# M4_Sensors.net
KiCad netlist of a schematic drawn in Altium Designer
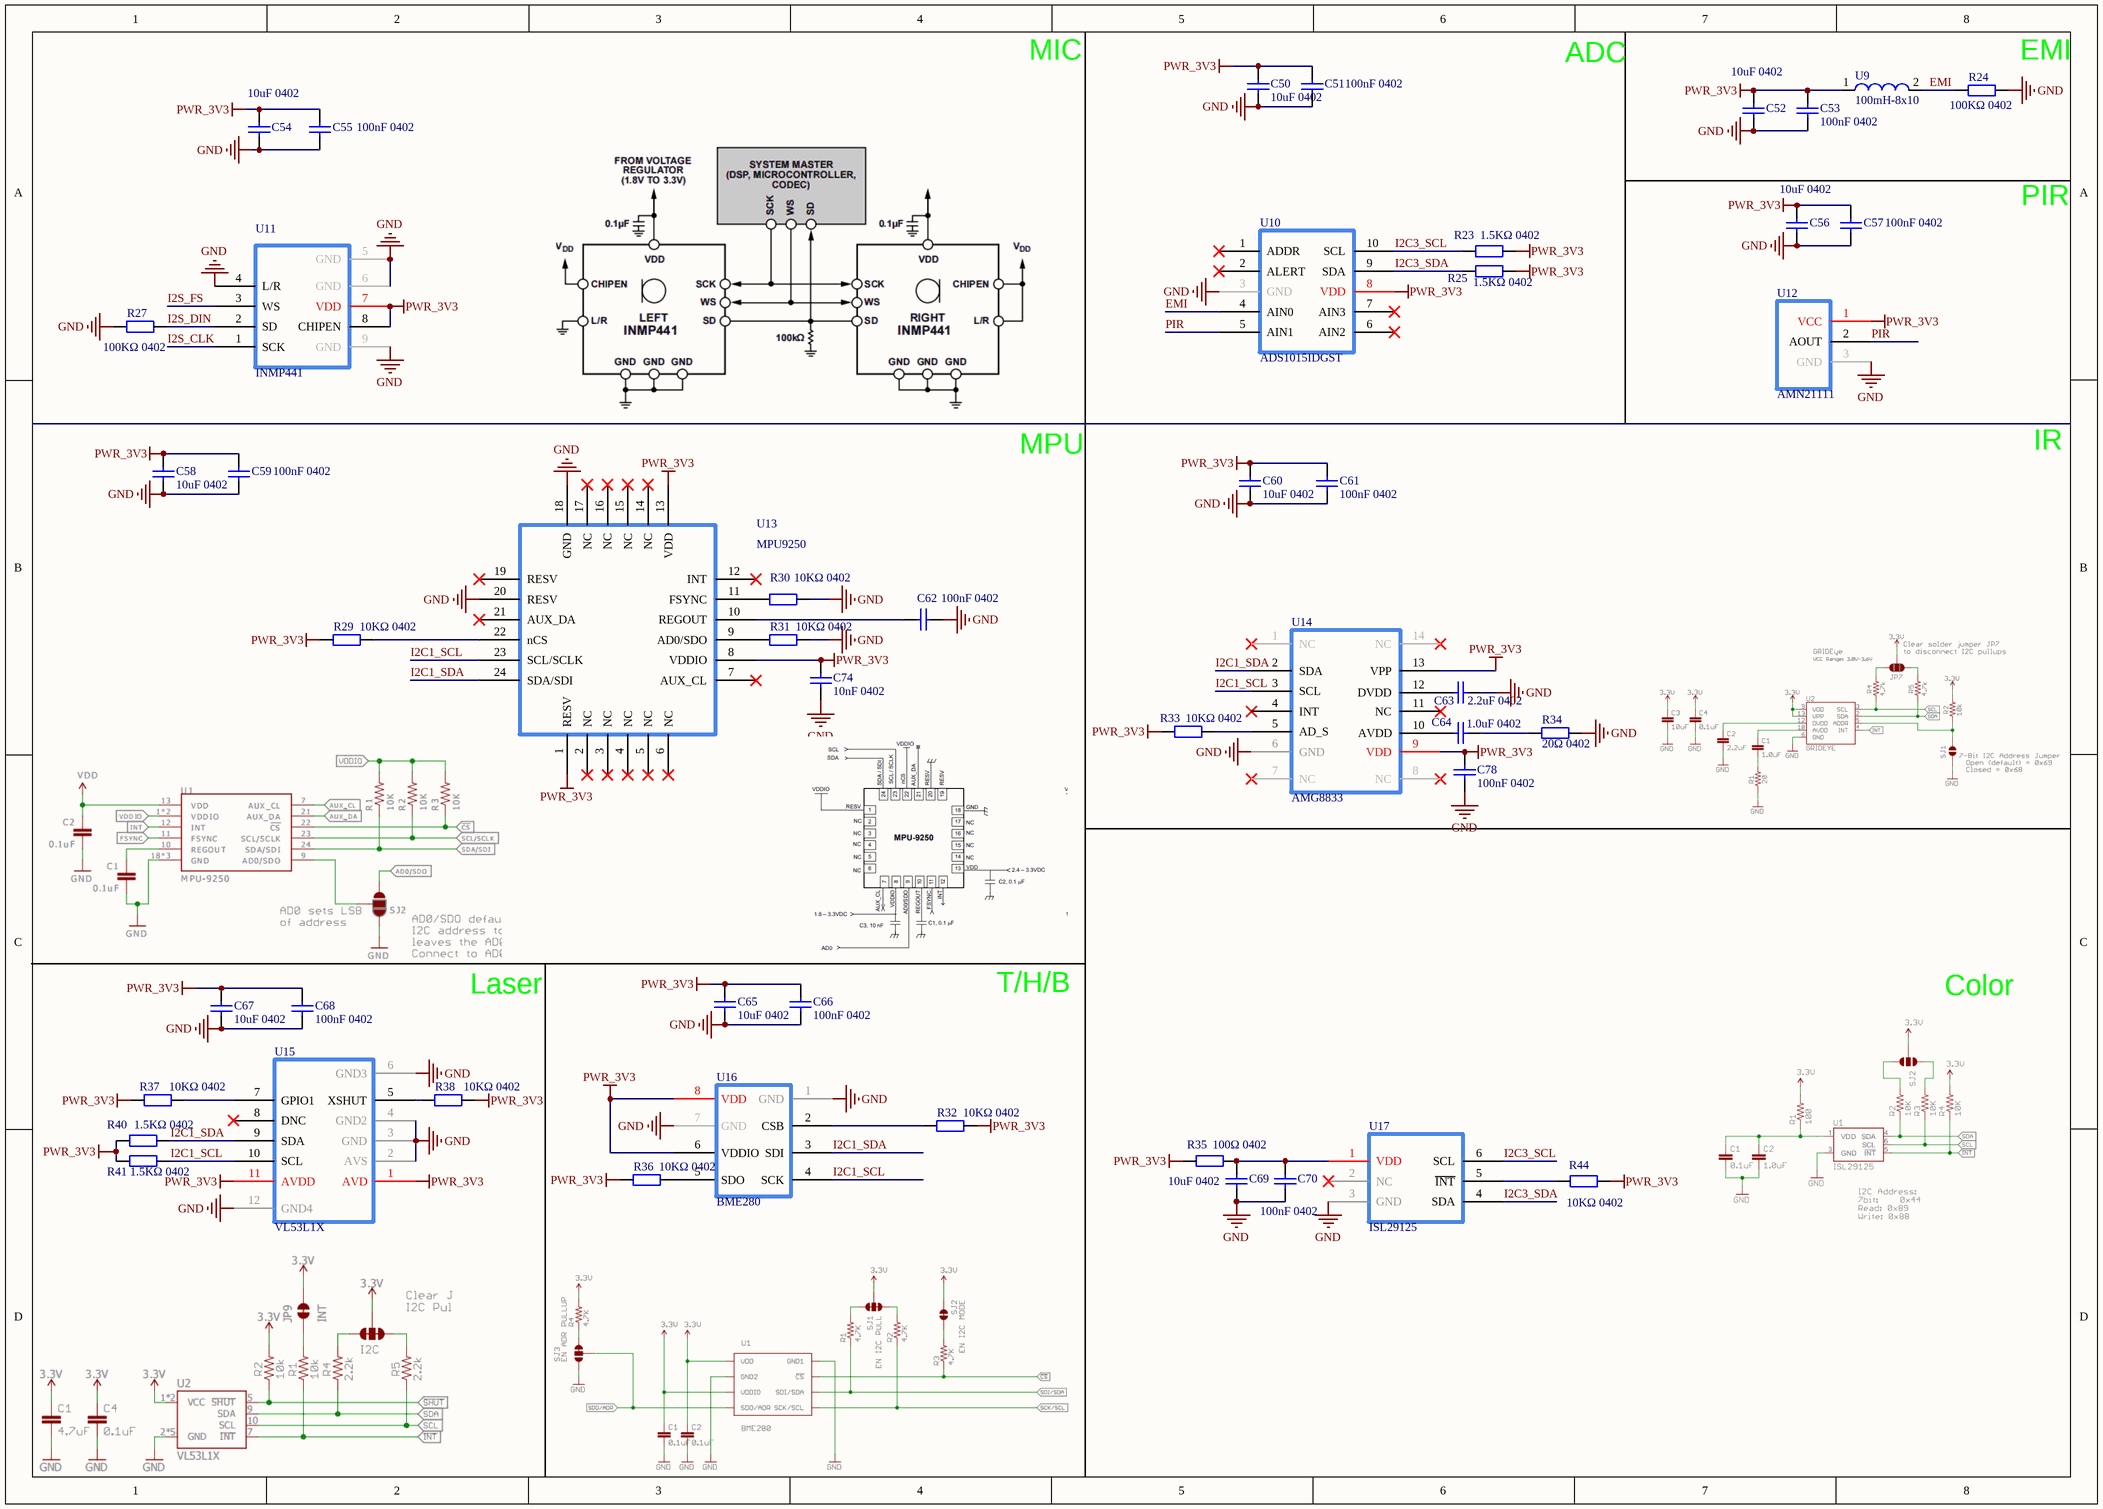
[diagram p0: M4_Sensors.SchDoc]

(export (version "E")
  (design (tool "Eeschema 10.0.6"))
  (components
    (comp (ref "C50")
      (value "10uF 0402")
      (footprint "0402_C")
      (description "贴片电容")
      (libsource (lib "Miscellaneous Devices LC") (part "0402 10uF (106) 20% 6.3V"))
    )
    (comp (ref "C51")
      (value "100nF 0402")
      (footprint "0402_C")
      (description "贴片电容")
      (libsource (lib "Miscellaneous Devices LC") (part "0402 100nF (104) 10% 16V"))
    )
    (comp (ref "C52")
      (value "10uF 0402")
      (footprint "0402_C")
      (description "贴片电容")
      (libsource (lib "Miscellaneous Devices LC") (part "0402 10uF (106) 20% 6.3V"))
    )
    (comp (ref "C53")
      (value "100nF 0402")
      (footprint "0402_C")
      (description "贴片电容")
      (libsource (lib "Miscellaneous Devices LC") (part "0402 100nF (104) 10% 16V"))
    )
    (comp (ref "C54")
      (value "10uF 0402")
      (footprint "0402_C")
      (description "贴片电容")
      (libsource (lib "Miscellaneous Devices LC") (part "0402 10uF (106) 20% 6.3V"))
    )
    (comp (ref "C55")
      (value "100nF 0402")
      (footprint "0402_C")
      (description "贴片电容")
      (libsource (lib "Miscellaneous Devices LC") (part "0402 100nF (104) 10% 16V"))
    )
    (comp (ref "C56")
      (value "10uF 0402")
      (footprint "0402_C")
      (description "贴片电容")
      (libsource (lib "Miscellaneous Devices LC") (part "0402 10uF (106) 20% 6.3V"))
    )
    (comp (ref "C57")
      (value "100nF 0402")
      (footprint "0402_C")
      (description "贴片电容")
      (libsource (lib "Miscellaneous Devices LC") (part "0402 100nF (104) 10% 16V"))
    )
    (comp (ref "C58")
      (value "10uF 0402")
      (footprint "0402_C")
      (description "贴片电容")
      (libsource (lib "Miscellaneous Devices LC") (part "0402 10uF (106) 20% 6.3V"))
    )
    (comp (ref "C59")
      (value "100nF 0402")
      (footprint "0402_C")
      (description "贴片电容")
      (libsource (lib "Miscellaneous Devices LC") (part "0402 100nF (104) 10% 16V"))
    )
    (comp (ref "C60")
      (value "10uF 0402")
      (footprint "0402_C")
      (description "贴片电容")
      (libsource (lib "Miscellaneous Devices LC") (part "0402 10uF (106) 20% 6.3V"))
    )
    (comp (ref "C61")
      (value "100nF 0402")
      (footprint "0402_C")
      (description "贴片电容")
      (libsource (lib "Miscellaneous Devices LC") (part "0402 100nF (104) 10% 16V"))
    )
    (comp (ref "C62")
      (value "100nF 0402")
      (footprint "0402_C")
      (description "贴片电容")
      (libsource (lib "Miscellaneous Devices LC") (part "0402 100nF (104) 10% 16V"))
    )
    (comp (ref "C63")
      (value "2.2uF 0402")
      (footprint "0402_C")
      (description "贴片电容")
      (libsource (lib "Miscellaneous Devices LC") (part "0402 4.7uF (475) 20% 10V"))
    )
    (comp (ref "C64")
      (value "1.0uF 0402")
      (footprint "0402_C")
      (description "贴片电容")
      (libsource (lib "Miscellaneous Devices LC") (part "0402 1.0uF (105) 10% 25V"))
    )
    (comp (ref "C65")
      (value "10uF 0402")
      (footprint "0402_C")
      (description "贴片电容")
      (libsource (lib "Miscellaneous Devices LC") (part "0402 10uF (106) 20% 6.3V"))
    )
    (comp (ref "C66")
      (value "100nF 0402")
      (footprint "0402_C")
      (description "贴片电容")
      (libsource (lib "Miscellaneous Devices LC") (part "0402 100nF (104) 10% 16V"))
    )
    (comp (ref "C67")
      (value "10uF 0402")
      (footprint "0402_C")
      (description "贴片电容")
      (libsource (lib "Miscellaneous Devices LC") (part "0402 10uF (106) 20% 6.3V"))
    )
    (comp (ref "C68")
      (value "100nF 0402")
      (footprint "0402_C")
      (description "贴片电容")
      (libsource (lib "Miscellaneous Devices LC") (part "0402 100nF (104) 10% 16V"))
    )
    (comp (ref "C69")
      (value "10uF 0402")
      (footprint "0402_C")
      (description "贴片电容")
      (libsource (lib "Miscellaneous Devices LC") (part "0402 10uF (106) 20% 6.3V"))
    )
    (comp (ref "C70")
      (value "100nF 0402")
      (footprint "0402_C")
      (description "贴片电容")
      (libsource (lib "Miscellaneous Devices LC") (part "0402 100nF (104) 10% 16V"))
    )
    (comp (ref "C74")
      (value "10nF 0402")
      (footprint "0402_C")
      (description "贴片电容")
      (libsource (lib "Miscellaneous Devices LC") (part "0402 10nF (103) 10% 50V"))
    )
    (comp (ref "C78")
      (value "100nF 0402")
      (footprint "0402_C")
      (description "贴片电容")
      (libsource (lib "Miscellaneous Devices LC") (part "0402 100nF (104) 10% 16V"))
    )
    (comp (ref "R23")
      (value "1.5KΩ 0402")
      (footprint "0402_R")
      (description "贴片电阻")
      (libsource (lib "Miscellaneous Devices LC") (part "0402 1.5KΩ (1501) 1%"))
    )
    (comp (ref "R24")
      (value "100KΩ 0402")
      (footprint "0402_R")
      (description "贴片电阻")
      (libsource (lib "") (part "0402 100KΩ (1003) 1%_1"))
    )
    (comp (ref "R25")
      (value "1.5KΩ 0402")
      (footprint "0402_R")
      (description "贴片电阻")
      (libsource (lib "Miscellaneous Devices LC") (part "0402 1.5KΩ (1501) 1%"))
    )
    (comp (ref "R27")
      (value "100KΩ 0402")
      (footprint "0402_R")
      (description "贴片电阻")
      (libsource (lib "Miscellaneous Devices LC") (part "0402 100KΩ (1003) 1%"))
    )
    (comp (ref "R29")
      (value "10KΩ 0402")
      (footprint "0402_R")
      (description "贴片电阻")
      (libsource (lib "Miscellaneous Devices LC") (part "0402 10KΩ (1002) 1%"))
    )
    (comp (ref "R30")
      (value "10KΩ 0402")
      (footprint "0402_R")
      (description "贴片电阻")
      (libsource (lib "Miscellaneous Devices LC") (part "0402 10KΩ (1002) 1%"))
    )
    (comp (ref "R31")
      (value "10KΩ 0402")
      (footprint "0402_R")
      (description "贴片电阻")
      (libsource (lib "Miscellaneous Devices LC") (part "0402 10KΩ (1002) 1%"))
    )
    (comp (ref "R32")
      (value "10KΩ 0402")
      (footprint "0402_R")
      (description "贴片电阻")
      (libsource (lib "Miscellaneous Devices LC") (part "0402 10KΩ (1002) 1%"))
    )
    (comp (ref "R33")
      (value "10KΩ 0402")
      (footprint "0402_R")
      (description "贴片电阻")
      (libsource (lib "Miscellaneous Devices LC") (part "0402 10KΩ (1002) 1%"))
    )
    (comp (ref "R34")
      (value "20Ω 0402")
      (footprint "0402_R")
      (description "贴片电阻")
      (libsource (lib "Miscellaneous Devices LC") (part "0402 22Ω (22R0) 1%"))
    )
    (comp (ref "R35")
      (value "100Ω 0402")
      (footprint "0402_R")
      (description "贴片电阻")
      (libsource (lib "Miscellaneous Devices LC") (part "0402 100Ω (1000) 1%"))
    )
    (comp (ref "R36")
      (value "10KΩ 0402")
      (footprint "0402_R")
      (description "贴片电阻")
      (libsource (lib "Miscellaneous Devices LC") (part "0402 10KΩ (1002) 1%"))
    )
    (comp (ref "R37")
      (value "10KΩ 0402")
      (footprint "0402_R")
      (description "贴片电阻")
      (libsource (lib "Miscellaneous Devices LC") (part "0402 10KΩ (1002) 1%"))
    )
    (comp (ref "R38")
      (value "10KΩ 0402")
      (footprint "0402_R")
      (description "贴片电阻")
      (libsource (lib "Miscellaneous Devices LC") (part "0402 10KΩ (1002) 1%"))
    )
    (comp (ref "R40")
      (value "1.5KΩ 0402")
      (footprint "0402_R")
      (description "贴片电阻")
      (libsource (lib "Miscellaneous Devices LC") (part "0402 1.5KΩ (1501) 1%"))
    )
    (comp (ref "R41")
      (value "1.5KΩ 0402")
      (footprint "0402_R")
      (description "贴片电阻")
      (libsource (lib "Miscellaneous Devices LC") (part "0402 1.5KΩ (1501) 1%"))
    )
    (comp (ref "R44")
      (value "10KΩ 0402")
      (footprint "0402_R")
      (description "贴片电阻")
      (libsource (lib "Miscellaneous Devices LC") (part "0402 10KΩ (1002) 1%"))
    )
    (comp (ref "U9")
      (value "100mH-8x10")
      (footprint "100mH-8x10")
      (description "Sensor 100mH")
      (libsource (lib "Sensor") (part "100mH-8x10"))
    )
    (comp (ref "U10")
      (value "ADS1015IDGST")
      (footprint "ADS1015")
      (description "ADC 12Bit 4Channel")
      (fields (field (name "MF") "Texas Instruments"))
      (libsource (lib "Sensor") (part "ADS1015IDGST"))
    )
    (comp (ref "U11")
      (value "INMP441")
      (footprint "INMP441")
      (description "Sensor Microphone")
      (libsource (lib "Sensor") (part "INMP441"))
    )
    (comp (ref "U12")
      (value "AMN21111")
      (footprint "AMN21111")
      (description "Sensor PIR")
      (libsource (lib "Sensor") (part "AMN21111"))
    )
    (comp (ref "U13")
      (value "MPU9250")
      (footprint "MPU9250")
      (description "Sensor MPU")
      (libsource (lib "Sensor") (part "MPU9250"))
    )
    (comp (ref "U14")
      (value "AMG8833")
      (footprint "AMG8833")
      (description "Sensor IR")
      (libsource (lib "Sensor") (part "AMG8833"))
    )
    (comp (ref "U15")
      (value "VL53L1X")
      (footprint "VL53L1X")
      (description "Sensor Laser")
      (libsource (lib "Sensor") (part "VL53L1X"))
    )
    (comp (ref "U16")
      (value "BME280")
      (footprint "BME280")
      (description "Sensor T/H/B TOP View")
      (libsource (lib "Sensor") (part "BME280"))
    )
    (comp (ref "U17")
      (value "ISL29125")
      (footprint "ISL29125")
      (description "Sensor Color")
      (libsource (lib "Sensor") (part "ISL29125"))
    )
  )
  (nets
    (net (code "1") (name "/EMI") (class "Default")
      (node (ref "R24") (pin "1") (pinfunction "1_1") (pintype "passive"))
      (node (ref "U10") (pin "4") (pinfunction "AIN0_4") (pintype "passive"))
      (node (ref "U9") (pin "2") (pinfunction "2_2") (pintype "passive"))
    )
    (net (code "2") (name "/I2C1_SCL") (class "Default")
      (node (ref "R41") (pin "2") (pinfunction "2_2") (pintype "passive"))
      (node (ref "U13") (pin "23") (pinfunction "SCL/SCLK_23") (pintype "passive"))
      (node (ref "U14") (pin "3") (pinfunction "SCL_3") (pintype "passive"))
      (node (ref "U15") (pin "10") (pinfunction "SCL_10") (pintype "passive"))
      (node (ref "U16") (pin "4") (pinfunction "SCK_4") (pintype "passive"))
    )
    (net (code "3") (name "/I2C1_SDA") (class "Default")
      (node (ref "R40") (pin "2") (pinfunction "2_2") (pintype "passive"))
      (node (ref "U13") (pin "24") (pinfunction "SDA/SDI_24") (pintype "passive"))
      (node (ref "U14") (pin "2") (pinfunction "SDA_2") (pintype "passive"))
      (node (ref "U15") (pin "9") (pinfunction "SDA_9") (pintype "passive"))
      (node (ref "U16") (pin "3") (pinfunction "SDI_3") (pintype "passive"))
    )
    (net (code "4") (name "/I2C3_SCL") (class "Default")
      (node (ref "R23") (pin "1") (pinfunction "1_1") (pintype "passive"))
      (node (ref "U10") (pin "10") (pinfunction "SCL_10") (pintype "passive"))
      (node (ref "U17") (pin "6") (pinfunction "SCL_6") (pintype "passive"))
    )
    (net (code "5") (name "/I2C3_SDA") (class "Default")
      (node (ref "R25") (pin "1") (pinfunction "1_1") (pintype "passive"))
      (node (ref "U10") (pin "9") (pinfunction "SDA_9") (pintype "passive"))
      (node (ref "U17") (pin "4") (pinfunction "SDA_4") (pintype "passive"))
    )
    (net (code "6") (name "/I2S_CLK") (class "Default")
      (node (ref "U11") (pin "1") (pinfunction "SCK_1") (pintype "passive"))
    )
    (net (code "7") (name "/I2S_DIN") (class "Default")
      (node (ref "R27") (pin "1") (pinfunction "1_1") (pintype "passive"))
      (node (ref "U11") (pin "2") (pinfunction "SD_2") (pintype "passive"))
    )
    (net (code "8") (name "/I2S_FS") (class "Default")
      (node (ref "U11") (pin "3") (pinfunction "WS_3") (pintype "passive"))
    )
    (net (code "9") (name "/PIR") (class "Default")
      (node (ref "U10") (pin "5") (pinfunction "AIN1_5") (pintype "passive"))
      (node (ref "U12") (pin "2") (pinfunction "AOUT_2") (pintype "passive"))
    )
    (net (code "10") (name "GND") (class "Default")
      (node (ref "C50") (pin "1") (pinfunction "1_1") (pintype "passive"))
      (node (ref "C51") (pin "1") (pinfunction "1_1") (pintype "passive"))
      (node (ref "C52") (pin "1") (pinfunction "1_1") (pintype "passive"))
      (node (ref "C53") (pin "1") (pinfunction "1_1") (pintype "passive"))
      (node (ref "C54") (pin "1") (pinfunction "1_1") (pintype "passive"))
      (node (ref "C55") (pin "1") (pinfunction "1_1") (pintype "passive"))
      (node (ref "C56") (pin "1") (pinfunction "1_1") (pintype "passive"))
      (node (ref "C57") (pin "1") (pinfunction "1_1") (pintype "passive"))
      (node (ref "C58") (pin "2") (pinfunction "2_2") (pintype "passive"))
      (node (ref "C59") (pin "2") (pinfunction "2_2") (pintype "passive"))
      (node (ref "C60") (pin "2") (pinfunction "2_2") (pintype "passive"))
      (node (ref "C61") (pin "2") (pinfunction "2_2") (pintype "passive"))
      (node (ref "C62") (pin "2") (pinfunction "2_2") (pintype "passive"))
      (node (ref "C63") (pin "2") (pinfunction "2_2") (pintype "passive"))
      (node (ref "C65") (pin "2") (pinfunction "2_2") (pintype "passive"))
      (node (ref "C66") (pin "2") (pinfunction "2_2") (pintype "passive"))
      (node (ref "C67") (pin "1") (pinfunction "1_1") (pintype "passive"))
      (node (ref "C68") (pin "1") (pinfunction "1_1") (pintype "passive"))
      (node (ref "C69") (pin "2") (pinfunction "2_2") (pintype "passive"))
      (node (ref "C70") (pin "2") (pinfunction "2_2") (pintype "passive"))
      (node (ref "C74") (pin "1") (pinfunction "1_1") (pintype "passive"))
      (node (ref "C78") (pin "2") (pinfunction "2_2") (pintype "passive"))
      (node (ref "R24") (pin "2") (pinfunction "2_2") (pintype "passive"))
      (node (ref "R27") (pin "2") (pinfunction "2_2") (pintype "passive"))
      (node (ref "R30") (pin "2") (pinfunction "2_2") (pintype "passive"))
      (node (ref "R31") (pin "2") (pinfunction "2_2") (pintype "passive"))
      (node (ref "R34") (pin "2") (pinfunction "2_2") (pintype "passive"))
      (node (ref "U10") (pin "3") (pinfunction "GND_3") (pintype "passive"))
      (node (ref "U11") (pin "4") (pinfunction "L/R_4") (pintype "passive"))
      (node (ref "U11") (pin "5") (pinfunction "GND_5") (pintype "passive"))
      (node (ref "U11") (pin "6") (pinfunction "GND_6") (pintype "passive"))
      (node (ref "U11") (pin "9") (pinfunction "GND_9") (pintype "passive"))
      (node (ref "U12") (pin "3") (pinfunction "GND_3") (pintype "passive"))
      (node (ref "U13") (pin "18") (pinfunction "GND_18") (pintype "passive"))
      (node (ref "U13") (pin "20") (pinfunction "RESV_20") (pintype "passive"))
      (node (ref "U14") (pin "6") (pinfunction "GND_6") (pintype "passive"))
      (node (ref "U15") (pin "12") (pinfunction "GND4_12") (pintype "passive"))
      (node (ref "U15") (pin "2") (pinfunction "AVS_2") (pintype "passive"))
      (node (ref "U15") (pin "3") (pinfunction "GND_3") (pintype "passive"))
      (node (ref "U15") (pin "4") (pinfunction "GND2_4") (pintype "passive"))
      (node (ref "U15") (pin "6") (pinfunction "GND3_6") (pintype "passive"))
      (node (ref "U16") (pin "1") (pinfunction "GND_1") (pintype "passive"))
      (node (ref "U16") (pin "7") (pinfunction "GND_7") (pintype "passive"))
      (node (ref "U17") (pin "3") (pinfunction "GND_3") (pintype "passive"))
    )
    (net (code "11") (name "Net-(C64-Pad2)") (class "Default")
      (node (ref "C64") (pin "2") (pinfunction "2_2") (pintype "passive"))
      (node (ref "R34") (pin "1") (pinfunction "1_1") (pintype "passive"))
    )
    (net (code "12") (name "Net-(U13-AD0{slash}SDO)") (class "Default")
      (node (ref "R31") (pin "1") (pinfunction "1_1") (pintype "passive"))
      (node (ref "U13") (pin "9") (pinfunction "AD0/SDO_9") (pintype "passive"))
    )
    (net (code "13") (name "Net-(U13-FSYNC)") (class "Default")
      (node (ref "R30") (pin "1") (pinfunction "1_1") (pintype "passive"))
      (node (ref "U13") (pin "11") (pinfunction "FSYNC_11") (pintype "passive"))
    )
    (net (code "14") (name "Net-(U13-REGOUT)") (class "Default")
      (node (ref "C62") (pin "1") (pinfunction "1_1") (pintype "passive"))
      (node (ref "U13") (pin "10") (pinfunction "REGOUT_10") (pintype "passive"))
    )
    (net (code "15") (name "Net-(U13-nCS)") (class "Default")
      (node (ref "R29") (pin "2") (pinfunction "2_2") (pintype "passive"))
      (node (ref "U13") (pin "22") (pinfunction "nCS_22") (pintype "passive"))
    )
    (net (code "16") (name "Net-(U14-AD_S)") (class "Default")
      (node (ref "R33") (pin "2") (pinfunction "2_2") (pintype "passive"))
      (node (ref "U14") (pin "5") (pinfunction "AD_S_5") (pintype "passive"))
    )
    (net (code "17") (name "Net-(U14-AVDD)") (class "Default")
      (node (ref "C64") (pin "1") (pinfunction "1_1") (pintype "passive"))
      (node (ref "U14") (pin "10") (pinfunction "AVDD_10") (pintype "passive"))
    )
    (net (code "18") (name "Net-(U14-DVDD)") (class "Default")
      (node (ref "C63") (pin "1") (pinfunction "1_1") (pintype "passive"))
      (node (ref "U14") (pin "12") (pinfunction "DVDD_12") (pintype "passive"))
    )
    (net (code "19") (name "Net-(U15-GPIO1)") (class "Default")
      (node (ref "R37") (pin "2") (pinfunction "2_2") (pintype "passive"))
      (node (ref "U15") (pin "7") (pinfunction "GPIO1_7") (pintype "passive"))
    )
    (net (code "20") (name "Net-(U15-XSHUT)") (class "Default")
      (node (ref "R38") (pin "1") (pinfunction "1_1") (pintype "passive"))
      (node (ref "U15") (pin "5") (pinfunction "XSHUT_5") (pintype "passive"))
    )
    (net (code "21") (name "Net-(U16-CSB)") (class "Default")
      (node (ref "R32") (pin "1") (pinfunction "1_1") (pintype "passive"))
      (node (ref "U16") (pin "2") (pinfunction "CSB_2") (pintype "passive"))
    )
    (net (code "22") (name "Net-(U16-SDO)") (class "Default")
      (node (ref "R36") (pin "2") (pinfunction "2_2") (pintype "passive"))
      (node (ref "U16") (pin "5") (pinfunction "SDO_5") (pintype "passive"))
    )
    (net (code "23") (name "Net-(U17-VDD)") (class "Default")
      (node (ref "C69") (pin "1") (pinfunction "1_1") (pintype "passive"))
      (node (ref "C70") (pin "1") (pinfunction "1_1") (pintype "passive"))
      (node (ref "R35") (pin "2") (pinfunction "2_2") (pintype "passive"))
      (node (ref "U17") (pin "1") (pinfunction "VDD_1") (pintype "passive"))
    )
    (net (code "24") (name "Net-(U17-~{INT})") (class "Default")
      (node (ref "R44") (pin "1") (pinfunction "1_1") (pintype "passive"))
      (node (ref "U17") (pin "5") (pinfunction "~{INT}_5") (pintype "passive"))
    )
    (net (code "25") (name "PWR_3V3") (class "Default")
      (node (ref "C50") (pin "2") (pinfunction "2_2") (pintype "passive"))
      (node (ref "C51") (pin "2") (pinfunction "2_2") (pintype "passive"))
      (node (ref "C52") (pin "2") (pinfunction "2_2") (pintype "passive"))
      (node (ref "C53") (pin "2") (pinfunction "2_2") (pintype "passive"))
      (node (ref "C54") (pin "2") (pinfunction "2_2") (pintype "passive"))
      (node (ref "C55") (pin "2") (pinfunction "2_2") (pintype "passive"))
      (node (ref "C56") (pin "2") (pinfunction "2_2") (pintype "passive"))
      (node (ref "C57") (pin "2") (pinfunction "2_2") (pintype "passive"))
      (node (ref "C58") (pin "1") (pinfunction "1_1") (pintype "passive"))
      (node (ref "C59") (pin "1") (pinfunction "1_1") (pintype "passive"))
      (node (ref "C60") (pin "1") (pinfunction "1_1") (pintype "passive"))
      (node (ref "C61") (pin "1") (pinfunction "1_1") (pintype "passive"))
      (node (ref "C65") (pin "1") (pinfunction "1_1") (pintype "passive"))
      (node (ref "C66") (pin "1") (pinfunction "1_1") (pintype "passive"))
      (node (ref "C67") (pin "2") (pinfunction "2_2") (pintype "passive"))
      (node (ref "C68") (pin "2") (pinfunction "2_2") (pintype "passive"))
      (node (ref "C74") (pin "2") (pinfunction "2_2") (pintype "passive"))
      (node (ref "C78") (pin "1") (pinfunction "1_1") (pintype "passive"))
      (node (ref "R23") (pin "2") (pinfunction "2_2") (pintype "passive"))
      (node (ref "R25") (pin "2") (pinfunction "2_2") (pintype "passive"))
      (node (ref "R29") (pin "1") (pinfunction "1_1") (pintype "passive"))
      (node (ref "R32") (pin "2") (pinfunction "2_2") (pintype "passive"))
      (node (ref "R33") (pin "1") (pinfunction "1_1") (pintype "passive"))
      (node (ref "R35") (pin "1") (pinfunction "1_1") (pintype "passive"))
      (node (ref "R36") (pin "1") (pinfunction "1_1") (pintype "passive"))
      (node (ref "R37") (pin "1") (pinfunction "1_1") (pintype "passive"))
      (node (ref "R38") (pin "2") (pinfunction "2_2") (pintype "passive"))
      (node (ref "R40") (pin "1") (pinfunction "1_1") (pintype "passive"))
      (node (ref "R41") (pin "1") (pinfunction "1_1") (pintype "passive"))
      (node (ref "R44") (pin "2") (pinfunction "2_2") (pintype "passive"))
      (node (ref "U10") (pin "8") (pinfunction "VDD_8") (pintype "passive"))
      (node (ref "U11") (pin "7") (pinfunction "VDD_7") (pintype "passive"))
      (node (ref "U11") (pin "8") (pinfunction "CHIPEN_8") (pintype "passive"))
      (node (ref "U12") (pin "1") (pinfunction "VCC_1") (pintype "passive"))
      (node (ref "U13") (pin "1") (pinfunction "RESV_1") (pintype "passive"))
      (node (ref "U13") (pin "13") (pinfunction "VDD_13") (pintype "passive"))
      (node (ref "U13") (pin "8") (pinfunction "VDDIO_8") (pintype "passive"))
      (node (ref "U14") (pin "13") (pinfunction "VPP_13") (pintype "passive"))
      (node (ref "U14") (pin "9") (pinfunction "VDD_9") (pintype "passive"))
      (node (ref "U15") (pin "1") (pinfunction "AVD_1") (pintype "passive"))
      (node (ref "U15") (pin "11") (pinfunction "AVDD_11") (pintype "passive"))
      (node (ref "U16") (pin "6") (pinfunction "VDDIO_6") (pintype "passive"))
      (node (ref "U16") (pin "8") (pinfunction "VDD_8") (pintype "passive"))
      (node (ref "U9") (pin "1") (pinfunction "1_1") (pintype "passive"))
    )
    (net (code "26") (name "unconnected-(U10-ADDR-Pad1)") (class "Default")
      (node (ref "U10") (pin "1") (pinfunction "ADDR_1") (pintype "passive+no_connect"))
    )
    (net (code "27") (name "unconnected-(U10-AIN2-Pad6)") (class "Default")
      (node (ref "U10") (pin "6") (pinfunction "AIN2_6") (pintype "passive+no_connect"))
    )
    (net (code "28") (name "unconnected-(U10-AIN3-Pad7)") (class "Default")
      (node (ref "U10") (pin "7") (pinfunction "AIN3_7") (pintype "passive+no_connect"))
    )
    (net (code "29") (name "unconnected-(U10-ALERT-Pad2)") (class "Default")
      (node (ref "U10") (pin "2") (pinfunction "ALERT_2") (pintype "passive+no_connect"))
    )
    (net (code "30") (name "unconnected-(U13-AUX_CL-Pad7)") (class "Default")
      (node (ref "U13") (pin "7") (pinfunction "AUX_CL_7") (pintype "passive+no_connect"))
    )
    (net (code "31") (name "unconnected-(U13-AUX_DA-Pad21)") (class "Default")
      (node (ref "U13") (pin "21") (pinfunction "AUX_DA_21") (pintype "passive+no_connect"))
    )
    (net (code "32") (name "unconnected-(U13-INT-Pad12)") (class "Default")
      (node (ref "U13") (pin "12") (pinfunction "INT_12") (pintype "passive+no_connect"))
    )
    (net (code "33") (name "unconnected-(U13-NC-Pad2)") (class "Default")
      (node (ref "U13") (pin "2") (pinfunction "NC_2") (pintype "passive+no_connect"))
    )
    (net (code "34") (name "unconnected-(U13-NC-Pad3)") (class "Default")
      (node (ref "U13") (pin "3") (pinfunction "NC_3") (pintype "passive+no_connect"))
    )
    (net (code "35") (name "unconnected-(U13-NC-Pad4)") (class "Default")
      (node (ref "U13") (pin "4") (pinfunction "NC_4") (pintype "passive+no_connect"))
    )
    (net (code "36") (name "unconnected-(U13-NC-Pad5)") (class "Default")
      (node (ref "U13") (pin "5") (pinfunction "NC_5") (pintype "passive+no_connect"))
    )
    (net (code "37") (name "unconnected-(U13-NC-Pad6)") (class "Default")
      (node (ref "U13") (pin "6") (pinfunction "NC_6") (pintype "passive+no_connect"))
    )
    (net (code "38") (name "unconnected-(U13-NC-Pad14)") (class "Default")
      (node (ref "U13") (pin "14") (pinfunction "NC_14") (pintype "passive+no_connect"))
    )
    (net (code "39") (name "unconnected-(U13-NC-Pad15)") (class "Default")
      (node (ref "U13") (pin "15") (pinfunction "NC_15") (pintype "passive+no_connect"))
    )
    (net (code "40") (name "unconnected-(U13-NC-Pad16)") (class "Default")
      (node (ref "U13") (pin "16") (pinfunction "NC_16") (pintype "passive+no_connect"))
    )
    (net (code "41") (name "unconnected-(U13-NC-Pad17)") (class "Default")
      (node (ref "U13") (pin "17") (pinfunction "NC_17") (pintype "passive+no_connect"))
    )
    (net (code "42") (name "unconnected-(U13-RESV-Pad19)") (class "Default")
      (node (ref "U13") (pin "19") (pinfunction "RESV_19") (pintype "passive+no_connect"))
    )
    (net (code "43") (name "unconnected-(U14-INT-Pad4)") (class "Default")
      (node (ref "U14") (pin "4") (pinfunction "INT_4") (pintype "passive+no_connect"))
    )
    (net (code "44") (name "unconnected-(U14-NC-Pad1)") (class "Default")
      (node (ref "U14") (pin "1") (pinfunction "NC_1") (pintype "passive+no_connect"))
    )
    (net (code "45") (name "unconnected-(U14-NC-Pad7)") (class "Default")
      (node (ref "U14") (pin "7") (pinfunction "NC_7") (pintype "passive+no_connect"))
    )
    (net (code "46") (name "unconnected-(U14-NC-Pad8)") (class "Default")
      (node (ref "U14") (pin "8") (pinfunction "NC_8") (pintype "passive+no_connect"))
    )
    (net (code "47") (name "unconnected-(U14-NC-Pad11)") (class "Default")
      (node (ref "U14") (pin "11") (pinfunction "NC_11") (pintype "passive+no_connect"))
    )
    (net (code "48") (name "unconnected-(U14-NC-Pad14)") (class "Default")
      (node (ref "U14") (pin "14") (pinfunction "NC_14") (pintype "passive+no_connect"))
    )
    (net (code "49") (name "unconnected-(U15-DNC-Pad8)") (class "Default")
      (node (ref "U15") (pin "8") (pinfunction "DNC_8") (pintype "passive+no_connect"))
    )
    (net (code "50") (name "unconnected-(U17-NC-Pad2)") (class "Default")
      (node (ref "U17") (pin "2") (pinfunction "NC_2") (pintype "passive+no_connect"))
    )
  )
)
